# drive.net
KiCad netlist of a schematic drawn in Altium Designer
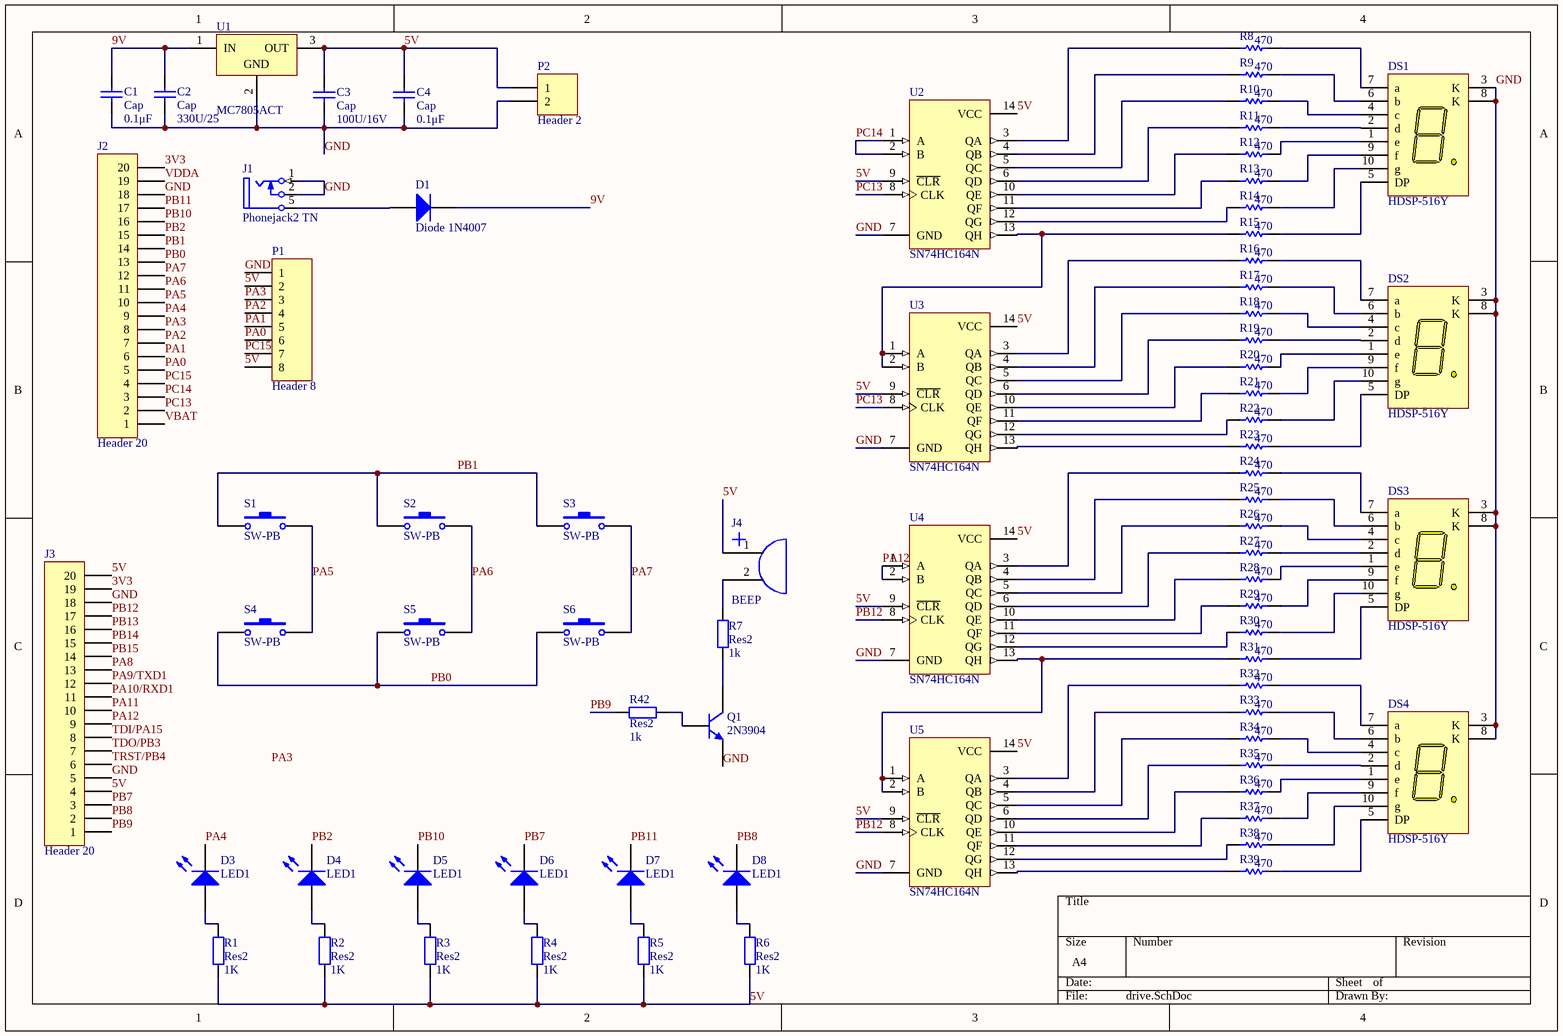
[diagram p0: drive.SchDoc]

(export (version "E")
  (design (tool "Eeschema 10.0.6"))
  (components
    (comp (ref "C1")
      (value "Cap")
      (footprint "RAD-0.3")
      (description "Capacitor")
      (fields (field (name "ALTIUM_VALUE") "0.1μF") (field (name "PUBLISHER") "Altium Limited"))
      (libsource (lib "Miscellaneous Devices") (part "Cap"))
    )
    (comp (ref "C2")
      (value "Cap")
      (footprint "RAD-0.3")
      (description "Capacitor")
      (fields (field (name "ALTIUM_VALUE") "330U/25") (field (name "PUBLISHER") "Altium Limited"))
      (libsource (lib "Miscellaneous Devices") (part "Cap"))
    )
    (comp (ref "C3")
      (value "Cap")
      (footprint "RAD-0.3")
      (description "Capacitor")
      (fields (field (name "ALTIUM_VALUE") "100U/16V") (field (name "PUBLISHER") "Altium Limited"))
      (libsource (lib "Miscellaneous Devices") (part "Cap"))
    )
    (comp (ref "C4")
      (value "Cap")
      (footprint "RAD-0.3")
      (description "Capacitor")
      (fields (field (name "ALTIUM_VALUE") "0.1μF") (field (name "PUBLISHER") "Altium Limited"))
      (libsource (lib "Miscellaneous Devices") (part "Cap"))
    )
    (comp (ref "D1")
      (value "Diode 1N4007")
      (footprint "DO-41")
      (description "1 Amp General Purpose Rectifier")
      (fields (field (name "PUBLISHER") "Altium Limited"))
      (libsource (lib "Miscellaneous Devices") (part "Diode 1N4007"))
    )
    (comp (ref "D3")
      (value "LED1")
      (footprint "LED-1")
      (description "Typical RED GaAs LED")
      (fields (field (name "PUBLISHER") "Altium Limited"))
      (libsource (lib "Miscellaneous Devices") (part "LED1"))
    )
    (comp (ref "D4")
      (value "LED1")
      (footprint "LED-1")
      (description "Typical RED GaAs LED")
      (fields (field (name "PUBLISHER") "Altium Limited"))
      (libsource (lib "Miscellaneous Devices") (part "LED1"))
    )
    (comp (ref "D5")
      (value "LED1")
      (footprint "LED-1")
      (description "Typical RED GaAs LED")
      (fields (field (name "PUBLISHER") "Altium Limited"))
      (libsource (lib "Miscellaneous Devices") (part "LED1"))
    )
    (comp (ref "D6")
      (value "LED1")
      (footprint "LED-1")
      (description "Typical RED GaAs LED")
      (fields (field (name "PUBLISHER") "Altium Limited"))
      (libsource (lib "Miscellaneous Devices") (part "LED1"))
    )
    (comp (ref "D7")
      (value "LED1")
      (footprint "LED-1")
      (description "Typical RED GaAs LED")
      (fields (field (name "PUBLISHER") "Altium Limited"))
      (libsource (lib "Miscellaneous Devices") (part "LED1"))
    )
    (comp (ref "D8")
      (value "LED1")
      (footprint "LED-1")
      (description "Typical RED GaAs LED")
      (fields (field (name "PUBLISHER") "Altium Limited"))
      (libsource (lib "Miscellaneous Devices") (part "LED1"))
    )
    (comp (ref "DS1")
      (value "HDSP-516Y")
      (footprint "Case-5")
      (description "13 mm Slim Font, Standard Current, Yellow 7-Segment Display: CC, RH DP")
      (fields (field (name "PUBLISHER") "Altium Limited"))
      (libsource (lib "Agilent LED Display 7-Segment, 1-Digit") (part "HDSP-516Y"))
    )
    (comp (ref "DS2")
      (value "HDSP-516Y")
      (footprint "Case-5")
      (description "13 mm Slim Font, Standard Current, Yellow 7-Segment Display: CC, RH DP")
      (fields (field (name "PUBLISHER") "Altium Limited"))
      (libsource (lib "Agilent LED Display 7-Segment, 1-Digit") (part "HDSP-516Y"))
    )
    (comp (ref "DS3")
      (value "HDSP-516Y")
      (footprint "Case-5")
      (description "13 mm Slim Font, Standard Current, Yellow 7-Segment Display: CC, RH DP")
      (fields (field (name "PUBLISHER") "Altium Limited"))
      (libsource (lib "Agilent LED Display 7-Segment, 1-Digit") (part "HDSP-516Y"))
    )
    (comp (ref "DS4")
      (value "HDSP-516Y")
      (footprint "Case-5")
      (description "13 mm Slim Font, Standard Current, Yellow 7-Segment Display: CC, RH DP")
      (fields (field (name "PUBLISHER") "Altium Limited"))
      (libsource (lib "Agilent LED Display 7-Segment, 1-Digit") (part "HDSP-516Y"))
    )
    (comp (ref "J1")
      (value "Phonejack2 TN")
      (footprint "DC-005")
      (description "Jack Socket, 1/4\" [6.5mm], Thru-Hole, Vertical, 2-Conductor with Tip closed")
      (fields (field (name "PUBLISHER") "Altium Limited"))
      (libsource (lib "Miscellaneous Connectors") (part "Phonejack2 TN"))
    )
    (comp (ref "J2")
      (value "Header 20")
      (footprint "HDR1X20")
      (description "Header, 20-Pin")
      (fields (field (name "PUBLISHER") "Altium Limited"))
      (libsource (lib "Miscellaneous Connectors") (part "Header 20"))
    )
    (comp (ref "J3")
      (value "Header 20")
      (footprint "HDR1X20")
      (description "Header, 20-Pin")
      (fields (field (name "PUBLISHER") "Altium Limited"))
      (libsource (lib "Miscellaneous Connectors") (part "Header 20"))
    )
    (comp (ref "J4")
      (value "BEEP")
      (footprint "Beep")
      (description "蜂鸣器")
      (libsource (lib "TSLone") (part "BEEP"))
    )
    (comp (ref "P1")
      (value "Header 8")
      (footprint "HDR1X8")
      (description "Header, 8-Pin")
      (fields (field (name "PUBLISHER") "Altium Limited"))
      (libsource (lib "Miscellaneous Connectors") (part "Header 8"))
    )
    (comp (ref "P2")
      (value "Header 2")
      (footprint "HDR1X2")
      (description "Header, 2-Pin")
      (fields (field (name "PUBLISHER") "Altium Limited"))
      (libsource (lib "Miscellaneous Connectors") (part "Header 2"))
    )
    (comp (ref "Q1")
      (value "2N3904")
      (footprint "TO-92A")
      (description "NPN General Purpose Amplifier")
      (fields (field (name "PUBLISHER") "Altium Limited"))
      (libsource (lib "Miscellaneous Devices") (part "2N3904"))
    )
    (comp (ref "R1")
      (value "Res2")
      (footprint "AXIAL-0.4")
      (description "Resistor")
      (fields (field (name "ALTIUM_VALUE") "1K") (field (name "PUBLISHER") "Altium Limited"))
      (libsource (lib "Miscellaneous Devices") (part "Res2"))
    )
    (comp (ref "R2")
      (value "Res2")
      (footprint "AXIAL-0.4")
      (description "Resistor")
      (fields (field (name "ALTIUM_VALUE") "1K") (field (name "PUBLISHER") "Altium Limited"))
      (libsource (lib "Miscellaneous Devices") (part "Res2"))
    )
    (comp (ref "R3")
      (value "Res2")
      (footprint "AXIAL-0.4")
      (description "Resistor")
      (fields (field (name "ALTIUM_VALUE") "1K") (field (name "PUBLISHER") "Altium Limited"))
      (libsource (lib "Miscellaneous Devices") (part "Res2"))
    )
    (comp (ref "R4")
      (value "Res2")
      (footprint "AXIAL-0.4")
      (description "Resistor")
      (fields (field (name "ALTIUM_VALUE") "1K") (field (name "PUBLISHER") "Altium Limited"))
      (libsource (lib "Miscellaneous Devices") (part "Res2"))
    )
    (comp (ref "R5")
      (value "Res2")
      (footprint "AXIAL-0.4")
      (description "Resistor")
      (fields (field (name "ALTIUM_VALUE") "1K") (field (name "PUBLISHER") "Altium Limited"))
      (libsource (lib "Miscellaneous Devices") (part "Res2"))
    )
    (comp (ref "R6")
      (value "Res2")
      (footprint "AXIAL-0.4")
      (description "Resistor")
      (fields (field (name "ALTIUM_VALUE") "1K") (field (name "PUBLISHER") "Altium Limited"))
      (libsource (lib "Miscellaneous Devices") (part "Res2"))
    )
    (comp (ref "R7")
      (value "Res2")
      (footprint "AXIAL-0.4")
      (description "Resistor")
      (fields (field (name "ALTIUM_VALUE") "1k") (field (name "PUBLISHER") "Altium Limited"))
      (libsource (lib "Miscellaneous Devices") (part "Res2"))
    )
    (comp (ref "R8")
      (value "470")
      (footprint "AXIAL-0.3")
      (description "Resistor")
      (fields (field (name "Comment") "Res1") (field (name "PUBLISHER") "Altium Limited"))
      (libsource (lib "Miscellaneous Devices") (part "Res1"))
    )
    (comp (ref "R9")
      (value "470")
      (footprint "AXIAL-0.3")
      (description "Resistor")
      (fields (field (name "Comment") "Res1") (field (name "PUBLISHER") "Altium Limited"))
      (libsource (lib "Miscellaneous Devices") (part "Res1"))
    )
    (comp (ref "R10")
      (value "470")
      (footprint "AXIAL-0.3")
      (description "Resistor")
      (fields (field (name "Comment") "Res1") (field (name "PUBLISHER") "Altium Limited"))
      (libsource (lib "Miscellaneous Devices") (part "Res1"))
    )
    (comp (ref "R11")
      (value "470")
      (footprint "AXIAL-0.3")
      (description "Resistor")
      (fields (field (name "Comment") "Res1") (field (name "PUBLISHER") "Altium Limited"))
      (libsource (lib "Miscellaneous Devices") (part "Res1"))
    )
    (comp (ref "R12")
      (value "470")
      (footprint "AXIAL-0.3")
      (description "Resistor")
      (fields (field (name "Comment") "Res1") (field (name "PUBLISHER") "Altium Limited"))
      (libsource (lib "Miscellaneous Devices") (part "Res1"))
    )
    (comp (ref "R13")
      (value "470")
      (footprint "AXIAL-0.3")
      (description "Resistor")
      (fields (field (name "Comment") "Res1") (field (name "PUBLISHER") "Altium Limited"))
      (libsource (lib "Miscellaneous Devices") (part "Res1"))
    )
    (comp (ref "R14")
      (value "470")
      (footprint "AXIAL-0.3")
      (description "Resistor")
      (fields (field (name "Comment") "Res1") (field (name "PUBLISHER") "Altium Limited"))
      (libsource (lib "Miscellaneous Devices") (part "Res1"))
    )
    (comp (ref "R15")
      (value "470")
      (footprint "AXIAL-0.3")
      (description "Resistor")
      (fields (field (name "Comment") "Res1") (field (name "PUBLISHER") "Altium Limited"))
      (libsource (lib "Miscellaneous Devices") (part "Res1"))
    )
    (comp (ref "R16")
      (value "470")
      (footprint "AXIAL-0.3")
      (description "Resistor")
      (fields (field (name "Comment") "Res1") (field (name "PUBLISHER") "Altium Limited"))
      (libsource (lib "Miscellaneous Devices") (part "Res1"))
    )
    (comp (ref "R17")
      (value "470")
      (footprint "AXIAL-0.3")
      (description "Resistor")
      (fields (field (name "Comment") "Res1") (field (name "PUBLISHER") "Altium Limited"))
      (libsource (lib "Miscellaneous Devices") (part "Res1"))
    )
    (comp (ref "R18")
      (value "470")
      (footprint "AXIAL-0.3")
      (description "Resistor")
      (fields (field (name "Comment") "Res1") (field (name "PUBLISHER") "Altium Limited"))
      (libsource (lib "Miscellaneous Devices") (part "Res1"))
    )
    (comp (ref "R19")
      (value "470")
      (footprint "AXIAL-0.3")
      (description "Resistor")
      (fields (field (name "Comment") "Res1") (field (name "PUBLISHER") "Altium Limited"))
      (libsource (lib "Miscellaneous Devices") (part "Res1"))
    )
    (comp (ref "R20")
      (value "470")
      (footprint "AXIAL-0.3")
      (description "Resistor")
      (fields (field (name "Comment") "Res1") (field (name "PUBLISHER") "Altium Limited"))
      (libsource (lib "Miscellaneous Devices") (part "Res1"))
    )
    (comp (ref "R21")
      (value "470")
      (footprint "AXIAL-0.3")
      (description "Resistor")
      (fields (field (name "Comment") "Res1") (field (name "PUBLISHER") "Altium Limited"))
      (libsource (lib "Miscellaneous Devices") (part "Res1"))
    )
    (comp (ref "R22")
      (value "470")
      (footprint "AXIAL-0.3")
      (description "Resistor")
      (fields (field (name "Comment") "Res1") (field (name "PUBLISHER") "Altium Limited"))
      (libsource (lib "Miscellaneous Devices") (part "Res1"))
    )
    (comp (ref "R23")
      (value "470")
      (footprint "AXIAL-0.3")
      (description "Resistor")
      (fields (field (name "Comment") "Res1") (field (name "PUBLISHER") "Altium Limited"))
      (libsource (lib "Miscellaneous Devices") (part "Res1"))
    )
    (comp (ref "R24")
      (value "470")
      (footprint "AXIAL-0.3")
      (description "Resistor")
      (fields (field (name "Comment") "Res1") (field (name "PUBLISHER") "Altium Limited"))
      (libsource (lib "Miscellaneous Devices") (part "Res1"))
    )
    (comp (ref "R25")
      (value "470")
      (footprint "AXIAL-0.3")
      (description "Resistor")
      (fields (field (name "Comment") "Res1") (field (name "PUBLISHER") "Altium Limited"))
      (libsource (lib "Miscellaneous Devices") (part "Res1"))
    )
    (comp (ref "R26")
      (value "470")
      (footprint "AXIAL-0.3")
      (description "Resistor")
      (fields (field (name "Comment") "Res1") (field (name "PUBLISHER") "Altium Limited"))
      (libsource (lib "Miscellaneous Devices") (part "Res1"))
    )
    (comp (ref "R27")
      (value "470")
      (footprint "AXIAL-0.3")
      (description "Resistor")
      (fields (field (name "Comment") "Res1") (field (name "PUBLISHER") "Altium Limited"))
      (libsource (lib "Miscellaneous Devices") (part "Res1"))
    )
    (comp (ref "R28")
      (value "470")
      (footprint "AXIAL-0.3")
      (description "Resistor")
      (fields (field (name "Comment") "Res1") (field (name "PUBLISHER") "Altium Limited"))
      (libsource (lib "Miscellaneous Devices") (part "Res1"))
    )
    (comp (ref "R29")
      (value "470")
      (footprint "AXIAL-0.3")
      (description "Resistor")
      (fields (field (name "Comment") "Res1") (field (name "PUBLISHER") "Altium Limited"))
      (libsource (lib "Miscellaneous Devices") (part "Res1"))
    )
    (comp (ref "R30")
      (value "470")
      (footprint "AXIAL-0.3")
      (description "Resistor")
      (fields (field (name "Comment") "Res1") (field (name "PUBLISHER") "Altium Limited"))
      (libsource (lib "Miscellaneous Devices") (part "Res1"))
    )
    (comp (ref "R31")
      (value "470")
      (footprint "AXIAL-0.3")
      (description "Resistor")
      (fields (field (name "Comment") "Res1") (field (name "PUBLISHER") "Altium Limited"))
      (libsource (lib "Miscellaneous Devices") (part "Res1"))
    )
    (comp (ref "R32")
      (value "470")
      (footprint "AXIAL-0.3")
      (description "Resistor")
      (fields (field (name "Comment") "Res1") (field (name "PUBLISHER") "Altium Limited"))
      (libsource (lib "Miscellaneous Devices") (part "Res1"))
    )
    (comp (ref "R33")
      (value "470")
      (footprint "AXIAL-0.3")
      (description "Resistor")
      (fields (field (name "Comment") "Res1") (field (name "PUBLISHER") "Altium Limited"))
      (libsource (lib "Miscellaneous Devices") (part "Res1"))
    )
    (comp (ref "R34")
      (value "470")
      (footprint "AXIAL-0.3")
      (description "Resistor")
      (fields (field (name "Comment") "Res1") (field (name "PUBLISHER") "Altium Limited"))
      (libsource (lib "Miscellaneous Devices") (part "Res1"))
    )
    (comp (ref "R35")
      (value "470")
      (footprint "AXIAL-0.3")
      (description "Resistor")
      (fields (field (name "Comment") "Res1") (field (name "PUBLISHER") "Altium Limited"))
      (libsource (lib "Miscellaneous Devices") (part "Res1"))
    )
    (comp (ref "R36")
      (value "470")
      (footprint "AXIAL-0.3")
      (description "Resistor")
      (fields (field (name "Comment") "Res1") (field (name "PUBLISHER") "Altium Limited"))
      (libsource (lib "Miscellaneous Devices") (part "Res1"))
    )
    (comp (ref "R37")
      (value "470")
      (footprint "AXIAL-0.3")
      (description "Resistor")
      (fields (field (name "Comment") "Res1") (field (name "PUBLISHER") "Altium Limited"))
      (libsource (lib "Miscellaneous Devices") (part "Res1"))
    )
    (comp (ref "R38")
      (value "470")
      (footprint "AXIAL-0.3")
      (description "Resistor")
      (fields (field (name "Comment") "Res1") (field (name "PUBLISHER") "Altium Limited"))
      (libsource (lib "Miscellaneous Devices") (part "Res1"))
    )
    (comp (ref "R39")
      (value "470")
      (footprint "AXIAL-0.3")
      (description "Resistor")
      (fields (field (name "Comment") "Res1") (field (name "PUBLISHER") "Altium Limited"))
      (libsource (lib "Miscellaneous Devices") (part "Res1"))
    )
    (comp (ref "R42")
      (value "Res2")
      (footprint "AXIAL-0.4")
      (description "Resistor")
      (fields (field (name "ALTIUM_VALUE") "1k") (field (name "PUBLISHER") "Altium Limited"))
      (libsource (lib "") (part "Res2_1"))
    )
    (comp (ref "S1")
      (value "SW-PB")
      (footprint "SW9")
      (description "微动开关")
      (fields (field (name "PUBLISHER") "Altium Limited"))
      (libsource (lib "TSLone") (part "SW-PB"))
    )
    (comp (ref "S2")
      (value "SW-PB")
      (footprint "SW9")
      (description "微动开关")
      (fields (field (name "PUBLISHER") "Altium Limited"))
      (libsource (lib "TSLone") (part "SW-PB"))
    )
    (comp (ref "S3")
      (value "SW-PB")
      (footprint "SW9")
      (description "微动开关")
      (fields (field (name "PUBLISHER") "Altium Limited"))
      (libsource (lib "TSLone") (part "SW-PB"))
    )
    (comp (ref "S4")
      (value "SW-PB")
      (footprint "SW9")
      (description "微动开关")
      (fields (field (name "PUBLISHER") "Altium Limited"))
      (libsource (lib "TSLone") (part "SW-PB"))
    )
    (comp (ref "S5")
      (value "SW-PB")
      (footprint "SW9")
      (description "微动开关")
      (fields (field (name "PUBLISHER") "Altium Limited"))
      (libsource (lib "TSLone") (part "SW-PB"))
    )
    (comp (ref "S6")
      (value "SW-PB")
      (footprint "SW9")
      (description "微动开关")
      (fields (field (name "PUBLISHER") "Altium Limited"))
      (libsource (lib "TSLone") (part "SW-PB"))
    )
    (comp (ref "U1")
      (value "MC7805ACT")
      (footprint "221A-06")
      (description "Three-Terminal Positive Voltage Regulator")
      (fields (field (name "PUBLISHER") "Altium Limited"))
      (libsource (lib "ON Semi Power Mgt Voltage Regulator") (part "MC7805ACT"))
    )
    (comp (ref "U2")
      (value "SN74HC164N")
      (footprint "N014")
      (description "8-Bit Parallel-Out Serial Shift Register")
      (fields (field (name "PUBLISHER") "Altium Limited"))
      (libsource (lib "TI Logic Register") (part "SN74HC164N"))
    )
    (comp (ref "U3")
      (value "SN74HC164N")
      (footprint "N014")
      (description "8-Bit Parallel-Out Serial Shift Register")
      (fields (field (name "PUBLISHER") "Altium Limited"))
      (libsource (lib "TI Logic Register") (part "SN74HC164N"))
    )
    (comp (ref "U4")
      (value "SN74HC164N")
      (footprint "N014")
      (description "8-Bit Parallel-Out Serial Shift Register")
      (fields (field (name "PUBLISHER") "Altium Limited"))
      (libsource (lib "TI Logic Register") (part "SN74HC164N"))
    )
    (comp (ref "U5")
      (value "SN74HC164N")
      (footprint "N014")
      (description "8-Bit Parallel-Out Serial Shift Register")
      (fields (field (name "PUBLISHER") "Altium Limited"))
      (libsource (lib "TI Logic Register") (part "SN74HC164N"))
    )
  )
  (nets
    (net (code "1") (name "/3V3") (class "Default")
      (node (ref "J2") (pin "20") (pinfunction "20_20") (pintype "passive"))
      (node (ref "J3") (pin "19") (pinfunction "19_19") (pintype "passive"))
    )
    (net (code "2") (name "/5V") (class "Default")
      (node (ref "C3") (pin "1") (pinfunction "1_1") (pintype "passive"))
      (node (ref "C4") (pin "1") (pinfunction "1_1") (pintype "passive"))
      (node (ref "J3") (pin "20") (pinfunction "20_20") (pintype "passive"))
      (node (ref "J3") (pin "4") (pinfunction "4_4") (pintype "passive"))
      (node (ref "J4") (pin "1") (pinfunction "0_1") (pintype "passive"))
      (node (ref "P1") (pin "2") (pinfunction "2_2") (pintype "passive"))
      (node (ref "P1") (pin "8") (pinfunction "8_8") (pintype "passive"))
      (node (ref "P2") (pin "1") (pinfunction "1_1") (pintype "passive"))
      (node (ref "R1") (pin "1") (pinfunction "1_1") (pintype "passive"))
      (node (ref "R2") (pin "1") (pinfunction "1_1") (pintype "passive"))
      (node (ref "R3") (pin "1") (pinfunction "1_1") (pintype "passive"))
      (node (ref "R4") (pin "1") (pinfunction "1_1") (pintype "passive"))
      (node (ref "R5") (pin "1") (pinfunction "1_1") (pintype "passive"))
      (node (ref "R6") (pin "1") (pinfunction "1_1") (pintype "passive"))
      (node (ref "U1") (pin "3") (pinfunction "OUT_3") (pintype "power_in"))
      (node (ref "U2") (pin "14") (pinfunction "VCC_14") (pintype "power_in"))
      (node (ref "U2") (pin "9") (pinfunction "~{CLR}_9") (pintype "input"))
      (node (ref "U3") (pin "14") (pinfunction "VCC_14") (pintype "power_in"))
      (node (ref "U3") (pin "9") (pinfunction "~{CLR}_9") (pintype "input"))
      (node (ref "U4") (pin "14") (pinfunction "VCC_14") (pintype "power_in"))
      (node (ref "U4") (pin "9") (pinfunction "~{CLR}_9") (pintype "input"))
      (node (ref "U5") (pin "14") (pinfunction "VCC_14") (pintype "power_in"))
      (node (ref "U5") (pin "9") (pinfunction "~{CLR}_9") (pintype "input"))
    )
    (net (code "3") (name "/9V") (class "Default")
      (node (ref "C1") (pin "1") (pinfunction "1_1") (pintype "passive"))
      (node (ref "C2") (pin "1") (pinfunction "1_1") (pintype "passive"))
      (node (ref "D1") (pin "2") (pinfunction "K_2") (pintype "passive"))
      (node (ref "U1") (pin "1") (pinfunction "IN_1") (pintype "power_in"))
    )
    (net (code "4") (name "/GND") (class "Default")
      (node (ref "C1") (pin "2") (pinfunction "2_2") (pintype "passive"))
      (node (ref "C2") (pin "2") (pinfunction "2_2") (pintype "passive"))
      (node (ref "C3") (pin "2") (pinfunction "2_2") (pintype "passive"))
      (node (ref "C4") (pin "2") (pinfunction "2_2") (pintype "passive"))
      (node (ref "DS1") (pin "3") (pinfunction "K_3") (pintype "passive"))
      (node (ref "DS1") (pin "8") (pinfunction "K_8") (pintype "passive"))
      (node (ref "DS2") (pin "3") (pinfunction "K_3") (pintype "passive"))
      (node (ref "DS2") (pin "8") (pinfunction "K_8") (pintype "passive"))
      (node (ref "DS3") (pin "3") (pinfunction "K_3") (pintype "passive"))
      (node (ref "DS3") (pin "8") (pinfunction "K_8") (pintype "passive"))
      (node (ref "DS4") (pin "3") (pinfunction "K_3") (pintype "passive"))
      (node (ref "DS4") (pin "8") (pinfunction "K_8") (pintype "passive"))
      (node (ref "J1") (pin "1") (pinfunction "T_1") (pintype "input"))
      (node (ref "J1") (pin "2") (pinfunction "TN_2") (pintype "passive"))
      (node (ref "J2") (pin "18") (pinfunction "18_18") (pintype "passive"))
      (node (ref "J3") (pin "18") (pinfunction "18_18") (pintype "passive"))
      (node (ref "J3") (pin "5") (pinfunction "5_5") (pintype "passive"))
      (node (ref "P1") (pin "1") (pinfunction "1_1") (pintype "passive"))
      (node (ref "P2") (pin "2") (pinfunction "2_2") (pintype "passive"))
      (node (ref "Q1") (pin "1") (pinfunction "E_1") (pintype "passive"))
      (node (ref "U1") (pin "2") (pinfunction "GND_2") (pintype "power_in"))
      (node (ref "U2") (pin "7") (pinfunction "GND_7") (pintype "power_in"))
      (node (ref "U3") (pin "7") (pinfunction "GND_7") (pintype "power_in"))
      (node (ref "U4") (pin "7") (pinfunction "GND_7") (pintype "power_in"))
      (node (ref "U5") (pin "7") (pinfunction "GND_7") (pintype "power_in"))
    )
    (net (code "5") (name "/PA0") (class "Default")
      (node (ref "J2") (pin "5") (pinfunction "5_5") (pintype "passive"))
      (node (ref "P1") (pin "6") (pinfunction "6_6") (pintype "passive"))
    )
    (net (code "6") (name "/PA1") (class "Default")
      (node (ref "J2") (pin "6") (pinfunction "6_6") (pintype "passive"))
      (node (ref "P1") (pin "5") (pinfunction "5_5") (pintype "passive"))
    )
    (net (code "7") (name "/PA2") (class "Default")
      (node (ref "J2") (pin "7") (pinfunction "7_7") (pintype "passive"))
      (node (ref "P1") (pin "4") (pinfunction "4_4") (pintype "passive"))
    )
    (net (code "8") (name "/PA3") (class "Default")
      (node (ref "J2") (pin "8") (pinfunction "8_8") (pintype "passive"))
      (node (ref "P1") (pin "3") (pinfunction "3_3") (pintype "passive"))
    )
    (net (code "9") (name "/PA4") (class "Default")
      (node (ref "D3") (pin "2") (pinfunction "K_2") (pintype "passive"))
      (node (ref "J2") (pin "9") (pinfunction "9_9") (pintype "passive"))
    )
    (net (code "10") (name "/PA5") (class "Default")
      (node (ref "J2") (pin "10") (pinfunction "10_10") (pintype "passive"))
      (node (ref "S1") (pin "2") (pinfunction "2_2") (pintype "passive"))
      (node (ref "S4") (pin "2") (pinfunction "2_2") (pintype "passive"))
    )
    (net (code "11") (name "/PA6") (class "Default")
      (node (ref "J2") (pin "11") (pinfunction "11_11") (pintype "passive"))
      (node (ref "S2") (pin "2") (pinfunction "2_2") (pintype "passive"))
      (node (ref "S5") (pin "2") (pinfunction "2_2") (pintype "passive"))
    )
    (net (code "12") (name "/PA7") (class "Default")
      (node (ref "J2") (pin "12") (pinfunction "12_12") (pintype "passive"))
      (node (ref "S3") (pin "2") (pinfunction "2_2") (pintype "passive"))
      (node (ref "S6") (pin "2") (pinfunction "2_2") (pintype "passive"))
    )
    (net (code "13") (name "/PA8") (class "Default")
      (node (ref "J3") (pin "13") (pinfunction "13_13") (pintype "passive"))
    )
    (net (code "14") (name "/PA9{slash}TXD1") (class "Default")
      (node (ref "J3") (pin "12") (pinfunction "12_12") (pintype "passive"))
    )
    (net (code "15") (name "/PA10{slash}RXD1") (class "Default")
      (node (ref "J3") (pin "11") (pinfunction "11_11") (pintype "passive"))
    )
    (net (code "16") (name "/PA11") (class "Default")
      (node (ref "J3") (pin "10") (pinfunction "10_10") (pintype "passive"))
    )
    (net (code "17") (name "/PA12") (class "Default")
      (node (ref "J3") (pin "9") (pinfunction "9_9") (pintype "passive"))
      (node (ref "U4") (pin "1") (pinfunction "A_1") (pintype "input"))
      (node (ref "U4") (pin "2") (pinfunction "B_2") (pintype "input"))
    )
    (net (code "18") (name "/PB0") (class "Default")
      (node (ref "J2") (pin "13") (pinfunction "13_13") (pintype "passive"))
      (node (ref "S4") (pin "1") (pinfunction "1_1") (pintype "passive"))
      (node (ref "S5") (pin "1") (pinfunction "1_1") (pintype "passive"))
      (node (ref "S6") (pin "1") (pinfunction "1_1") (pintype "passive"))
    )
    (net (code "19") (name "/PB1") (class "Default")
      (node (ref "J2") (pin "14") (pinfunction "14_14") (pintype "passive"))
      (node (ref "S1") (pin "1") (pinfunction "1_1") (pintype "passive"))
      (node (ref "S2") (pin "1") (pinfunction "1_1") (pintype "passive"))
      (node (ref "S3") (pin "1") (pinfunction "1_1") (pintype "passive"))
    )
    (net (code "20") (name "/PB2") (class "Default")
      (node (ref "D4") (pin "2") (pinfunction "K_2") (pintype "passive"))
      (node (ref "J2") (pin "15") (pinfunction "15_15") (pintype "passive"))
    )
    (net (code "21") (name "/PB7") (class "Default")
      (node (ref "D6") (pin "2") (pinfunction "K_2") (pintype "passive"))
      (node (ref "J3") (pin "3") (pinfunction "3_3") (pintype "passive"))
    )
    (net (code "22") (name "/PB8") (class "Default")
      (node (ref "D8") (pin "2") (pinfunction "K_2") (pintype "passive"))
      (node (ref "J3") (pin "2") (pinfunction "2_2") (pintype "passive"))
    )
    (net (code "23") (name "/PB9") (class "Default")
      (node (ref "J3") (pin "1") (pinfunction "1_1") (pintype "passive"))
      (node (ref "R42") (pin "2") (pinfunction "2_2") (pintype "passive"))
    )
    (net (code "24") (name "/PB10") (class "Default")
      (node (ref "D5") (pin "2") (pinfunction "K_2") (pintype "passive"))
      (node (ref "J2") (pin "16") (pinfunction "16_16") (pintype "passive"))
    )
    (net (code "25") (name "/PB11") (class "Default")
      (node (ref "D7") (pin "2") (pinfunction "K_2") (pintype "passive"))
      (node (ref "J2") (pin "17") (pinfunction "17_17") (pintype "passive"))
    )
    (net (code "26") (name "/PB12") (class "Default")
      (node (ref "J3") (pin "17") (pinfunction "17_17") (pintype "passive"))
      (node (ref "U4") (pin "8") (pinfunction "CLK_8") (pintype "input"))
      (node (ref "U5") (pin "8") (pinfunction "CLK_8") (pintype "input"))
    )
    (net (code "27") (name "/PB13") (class "Default")
      (node (ref "J3") (pin "16") (pinfunction "16_16") (pintype "passive"))
    )
    (net (code "28") (name "/PB14") (class "Default")
      (node (ref "J3") (pin "15") (pinfunction "15_15") (pintype "passive"))
    )
    (net (code "29") (name "/PB15") (class "Default")
      (node (ref "J3") (pin "14") (pinfunction "14_14") (pintype "passive"))
    )
    (net (code "30") (name "/PC13") (class "Default")
      (node (ref "J2") (pin "2") (pinfunction "2_2") (pintype "passive"))
      (node (ref "U2") (pin "8") (pinfunction "CLK_8") (pintype "input"))
      (node (ref "U3") (pin "8") (pinfunction "CLK_8") (pintype "input"))
    )
    (net (code "31") (name "/PC14") (class "Default")
      (node (ref "J2") (pin "3") (pinfunction "3_3") (pintype "passive"))
      (node (ref "U2") (pin "1") (pinfunction "A_1") (pintype "input"))
      (node (ref "U2") (pin "2") (pinfunction "B_2") (pintype "input"))
    )
    (net (code "32") (name "/PC15") (class "Default")
      (node (ref "J2") (pin "4") (pinfunction "4_4") (pintype "passive"))
      (node (ref "P1") (pin "7") (pinfunction "7_7") (pintype "passive"))
    )
    (net (code "33") (name "/TDI{slash}PA15") (class "Default")
      (node (ref "J3") (pin "8") (pinfunction "8_8") (pintype "passive"))
    )
    (net (code "34") (name "/TDO{slash}PB3") (class "Default")
      (node (ref "J3") (pin "7") (pinfunction "7_7") (pintype "passive"))
    )
    (net (code "35") (name "/TRST{slash}PB4") (class "Default")
      (node (ref "J3") (pin "6") (pinfunction "6_6") (pintype "passive"))
    )
    (net (code "36") (name "/VBAT") (class "Default")
      (node (ref "J2") (pin "1") (pinfunction "1_1") (pintype "passive"))
    )
    (net (code "37") (name "/VDDA") (class "Default")
      (node (ref "J2") (pin "19") (pinfunction "19_19") (pintype "passive"))
    )
    (net (code "38") (name "Net-(D1-A)") (class "Default")
      (node (ref "D1") (pin "1") (pinfunction "A_1") (pintype "passive"))
      (node (ref "J1") (pin "5") (pinfunction "S_5") (pintype "power_in"))
    )
    (net (code "39") (name "Net-(D3-A)") (class "Default")
      (node (ref "D3") (pin "1") (pinfunction "A_1") (pintype "passive"))
      (node (ref "R1") (pin "2") (pinfunction "2_2") (pintype "passive"))
    )
    (net (code "40") (name "Net-(D4-A)") (class "Default")
      (node (ref "D4") (pin "1") (pinfunction "A_1") (pintype "passive"))
      (node (ref "R2") (pin "2") (pinfunction "2_2") (pintype "passive"))
    )
    (net (code "41") (name "Net-(D5-A)") (class "Default")
      (node (ref "D5") (pin "1") (pinfunction "A_1") (pintype "passive"))
      (node (ref "R3") (pin "2") (pinfunction "2_2") (pintype "passive"))
    )
    (net (code "42") (name "Net-(D6-A)") (class "Default")
      (node (ref "D6") (pin "1") (pinfunction "A_1") (pintype "passive"))
      (node (ref "R4") (pin "2") (pinfunction "2_2") (pintype "passive"))
    )
    (net (code "43") (name "Net-(D7-A)") (class "Default")
      (node (ref "D7") (pin "1") (pinfunction "A_1") (pintype "passive"))
      (node (ref "R5") (pin "2") (pinfunction "2_2") (pintype "passive"))
    )
    (net (code "44") (name "Net-(D8-A)") (class "Default")
      (node (ref "D8") (pin "1") (pinfunction "A_1") (pintype "passive"))
      (node (ref "R6") (pin "2") (pinfunction "2_2") (pintype "passive"))
    )
    (net (code "45") (name "Net-(DS1-DP)") (class "Default")
      (node (ref "DS1") (pin "5") (pinfunction "DP_5") (pintype "passive"))
      (node (ref "R15") (pin "2") (pinfunction "2_2") (pintype "passive"))
    )
    (net (code "46") (name "Net-(DS1-a)") (class "Default")
      (node (ref "DS1") (pin "7") (pinfunction "a_7") (pintype "passive"))
      (node (ref "R8") (pin "2") (pinfunction "2_2") (pintype "passive"))
    )
    (net (code "47") (name "Net-(DS1-b)") (class "Default")
      (node (ref "DS1") (pin "6") (pinfunction "b_6") (pintype "passive"))
      (node (ref "R9") (pin "2") (pinfunction "2_2") (pintype "passive"))
    )
    (net (code "48") (name "Net-(DS1-c)") (class "Default")
      (node (ref "DS1") (pin "4") (pinfunction "c_4") (pintype "passive"))
      (node (ref "R10") (pin "2") (pinfunction "2_2") (pintype "passive"))
    )
    (net (code "49") (name "Net-(DS1-d)") (class "Default")
      (node (ref "DS1") (pin "2") (pinfunction "d_2") (pintype "passive"))
      (node (ref "R11") (pin "2") (pinfunction "2_2") (pintype "passive"))
    )
    (net (code "50") (name "Net-(DS1-e)") (class "Default")
      (node (ref "DS1") (pin "1") (pinfunction "e_1") (pintype "passive"))
      (node (ref "R12") (pin "2") (pinfunction "2_2") (pintype "passive"))
    )
    (net (code "51") (name "Net-(DS1-f)") (class "Default")
      (node (ref "DS1") (pin "9") (pinfunction "f_9") (pintype "passive"))
      (node (ref "R13") (pin "2") (pinfunction "2_2") (pintype "passive"))
    )
    (net (code "52") (name "Net-(DS1-g)") (class "Default")
      (node (ref "DS1") (pin "10") (pinfunction "g_10") (pintype "passive"))
      (node (ref "R14") (pin "2") (pinfunction "2_2") (pintype "passive"))
    )
    (net (code "53") (name "Net-(DS2-DP)") (class "Default")
      (node (ref "DS2") (pin "5") (pinfunction "DP_5") (pintype "passive"))
      (node (ref "R23") (pin "2") (pinfunction "2_2") (pintype "passive"))
    )
    (net (code "54") (name "Net-(DS2-a)") (class "Default")
      (node (ref "DS2") (pin "7") (pinfunction "a_7") (pintype "passive"))
      (node (ref "R16") (pin "2") (pinfunction "2_2") (pintype "passive"))
    )
    (net (code "55") (name "Net-(DS2-b)") (class "Default")
      (node (ref "DS2") (pin "6") (pinfunction "b_6") (pintype "passive"))
      (node (ref "R17") (pin "2") (pinfunction "2_2") (pintype "passive"))
    )
    (net (code "56") (name "Net-(DS2-c)") (class "Default")
      (node (ref "DS2") (pin "4") (pinfunction "c_4") (pintype "passive"))
      (node (ref "R18") (pin "2") (pinfunction "2_2") (pintype "passive"))
    )
    (net (code "57") (name "Net-(DS2-d)") (class "Default")
      (node (ref "DS2") (pin "2") (pinfunction "d_2") (pintype "passive"))
      (node (ref "R19") (pin "2") (pinfunction "2_2") (pintype "passive"))
    )
    (net (code "58") (name "Net-(DS2-e)") (class "Default")
      (node (ref "DS2") (pin "1") (pinfunction "e_1") (pintype "passive"))
      (node (ref "R20") (pin "2") (pinfunction "2_2") (pintype "passive"))
    )
    (net (code "59") (name "Net-(DS2-f)") (class "Default")
      (node (ref "DS2") (pin "9") (pinfunction "f_9") (pintype "passive"))
      (node (ref "R21") (pin "2") (pinfunction "2_2") (pintype "passive"))
    )
    (net (code "60") (name "Net-(DS2-g)") (class "Default")
      (node (ref "DS2") (pin "10") (pinfunction "g_10") (pintype "passive"))
      (node (ref "R22") (pin "2") (pinfunction "2_2") (pintype "passive"))
    )
    (net (code "61") (name "Net-(DS3-DP)") (class "Default")
      (node (ref "DS3") (pin "5") (pinfunction "DP_5") (pintype "passive"))
      (node (ref "R31") (pin "2") (pinfunction "2_2") (pintype "passive"))
    )
    (net (code "62") (name "Net-(DS3-a)") (class "Default")
      (node (ref "DS3") (pin "7") (pinfunction "a_7") (pintype "passive"))
      (node (ref "R24") (pin "2") (pinfunction "2_2") (pintype "passive"))
    )
    (net (code "63") (name "Net-(DS3-b)") (class "Default")
      (node (ref "DS3") (pin "6") (pinfunction "b_6") (pintype "passive"))
      (node (ref "R25") (pin "2") (pinfunction "2_2") (pintype "passive"))
    )
    (net (code "64") (name "Net-(DS3-c)") (class "Default")
      (node (ref "DS3") (pin "4") (pinfunction "c_4") (pintype "passive"))
      (node (ref "R26") (pin "2") (pinfunction "2_2") (pintype "passive"))
    )
    (net (code "65") (name "Net-(DS3-d)") (class "Default")
      (node (ref "DS3") (pin "2") (pinfunction "d_2") (pintype "passive"))
      (node (ref "R27") (pin "2") (pinfunction "2_2") (pintype "passive"))
    )
    (net (code "66") (name "Net-(DS3-e)") (class "Default")
      (node (ref "DS3") (pin "1") (pinfunction "e_1") (pintype "passive"))
      (node (ref "R28") (pin "2") (pinfunction "2_2") (pintype "passive"))
    )
    (net (code "67") (name "Net-(DS3-f)") (class "Default")
      (node (ref "DS3") (pin "9") (pinfunction "f_9") (pintype "passive"))
      (node (ref "R29") (pin "2") (pinfunction "2_2") (pintype "passive"))
    )
    (net (code "68") (name "Net-(DS3-g)") (class "Default")
      (node (ref "DS3") (pin "10") (pinfunction "g_10") (pintype "passive"))
      (node (ref "R30") (pin "2") (pinfunction "2_2") (pintype "passive"))
    )
    (net (code "69") (name "Net-(DS4-DP)") (class "Default")
      (node (ref "DS4") (pin "5") (pinfunction "DP_5") (pintype "passive"))
      (node (ref "R39") (pin "2") (pinfunction "2_2") (pintype "passive"))
    )
    (net (code "70") (name "Net-(DS4-a)") (class "Default")
      (node (ref "DS4") (pin "7") (pinfunction "a_7") (pintype "passive"))
      (node (ref "R32") (pin "2") (pinfunction "2_2") (pintype "passive"))
    )
    (net (code "71") (name "Net-(DS4-b)") (class "Default")
      (node (ref "DS4") (pin "6") (pinfunction "b_6") (pintype "passive"))
      (node (ref "R33") (pin "2") (pinfunction "2_2") (pintype "passive"))
    )
    (net (code "72") (name "Net-(DS4-c)") (class "Default")
      (node (ref "DS4") (pin "4") (pinfunction "c_4") (pintype "passive"))
      (node (ref "R34") (pin "2") (pinfunction "2_2") (pintype "passive"))
    )
    (net (code "73") (name "Net-(DS4-d)") (class "Default")
      (node (ref "DS4") (pin "2") (pinfunction "d_2") (pintype "passive"))
      (node (ref "R35") (pin "2") (pinfunction "2_2") (pintype "passive"))
    )
    (net (code "74") (name "Net-(DS4-e)") (class "Default")
      (node (ref "DS4") (pin "1") (pinfunction "e_1") (pintype "passive"))
      (node (ref "R36") (pin "2") (pinfunction "2_2") (pintype "passive"))
    )
    (net (code "75") (name "Net-(DS4-f)") (class "Default")
      (node (ref "DS4") (pin "9") (pinfunction "f_9") (pintype "passive"))
      (node (ref "R37") (pin "2") (pinfunction "2_2") (pintype "passive"))
    )
    (net (code "76") (name "Net-(DS4-g)") (class "Default")
      (node (ref "DS4") (pin "10") (pinfunction "g_10") (pintype "passive"))
      (node (ref "R38") (pin "2") (pinfunction "2_2") (pintype "passive"))
    )
    (net (code "77") (name "Net-(J4-1)") (class "Default")
      (node (ref "J4") (pin "2") (pinfunction "1_2") (pintype "passive"))
      (node (ref "R7") (pin "2") (pinfunction "2_2") (pintype "passive"))
    )
    (net (code "78") (name "Net-(Q1-B)") (class "Default")
      (node (ref "Q1") (pin "2") (pinfunction "B_2") (pintype "passive"))
      (node (ref "R42") (pin "1") (pinfunction "1_1") (pintype "passive"))
    )
    (net (code "79") (name "Net-(Q1-C)") (class "Default")
      (node (ref "Q1") (pin "3") (pinfunction "C_3") (pintype "passive"))
      (node (ref "R7") (pin "1") (pinfunction "1_1") (pintype "passive"))
    )
    (net (code "80") (name "Net-(U2-QA)") (class "Default")
      (node (ref "R8") (pin "1") (pinfunction "1_1") (pintype "passive"))
      (node (ref "U2") (pin "3") (pinfunction "QA_3") (pintype "output"))
    )
    (net (code "81") (name "Net-(U2-QB)") (class "Default")
      (node (ref "R9") (pin "1") (pinfunction "1_1") (pintype "passive"))
      (node (ref "U2") (pin "4") (pinfunction "QB_4") (pintype "output"))
    )
    (net (code "82") (name "Net-(U2-QC)") (class "Default")
      (node (ref "R10") (pin "1") (pinfunction "1_1") (pintype "passive"))
      (node (ref "U2") (pin "5") (pinfunction "QC_5") (pintype "output"))
    )
    (net (code "83") (name "Net-(U2-QD)") (class "Default")
      (node (ref "R11") (pin "1") (pinfunction "1_1") (pintype "passive"))
      (node (ref "U2") (pin "6") (pinfunction "QD_6") (pintype "output"))
    )
    (net (code "84") (name "Net-(U2-QE)") (class "Default")
      (node (ref "R12") (pin "1") (pinfunction "1_1") (pintype "passive"))
      (node (ref "U2") (pin "10") (pinfunction "QE_10") (pintype "output"))
    )
    (net (code "85") (name "Net-(U2-QF)") (class "Default")
      (node (ref "R13") (pin "1") (pinfunction "1_1") (pintype "passive"))
      (node (ref "U2") (pin "11") (pinfunction "QF_11") (pintype "output"))
    )
    (net (code "86") (name "Net-(U2-QG)") (class "Default")
      (node (ref "R14") (pin "1") (pinfunction "1_1") (pintype "passive"))
      (node (ref "U2") (pin "12") (pinfunction "QG_12") (pintype "output"))
    )
    (net (code "87") (name "Net-(U2-QH)") (class "Default")
      (node (ref "R15") (pin "1") (pinfunction "1_1") (pintype "passive"))
      (node (ref "U2") (pin "13") (pinfunction "QH_13") (pintype "output"))
      (node (ref "U3") (pin "1") (pinfunction "A_1") (pintype "input"))
      (node (ref "U3") (pin "2") (pinfunction "B_2") (pintype "input"))
    )
    (net (code "88") (name "Net-(U3-QA)") (class "Default")
      (node (ref "R16") (pin "1") (pinfunction "1_1") (pintype "passive"))
      (node (ref "U3") (pin "3") (pinfunction "QA_3") (pintype "output"))
    )
    (net (code "89") (name "Net-(U3-QB)") (class "Default")
      (node (ref "R17") (pin "1") (pinfunction "1_1") (pintype "passive"))
      (node (ref "U3") (pin "4") (pinfunction "QB_4") (pintype "output"))
    )
    (net (code "90") (name "Net-(U3-QC)") (class "Default")
      (node (ref "R18") (pin "1") (pinfunction "1_1") (pintype "passive"))
      (node (ref "U3") (pin "5") (pinfunction "QC_5") (pintype "output"))
    )
    (net (code "91") (name "Net-(U3-QD)") (class "Default")
      (node (ref "R19") (pin "1") (pinfunction "1_1") (pintype "passive"))
      (node (ref "U3") (pin "6") (pinfunction "QD_6") (pintype "output"))
    )
    (net (code "92") (name "Net-(U3-QE)") (class "Default")
      (node (ref "R20") (pin "1") (pinfunction "1_1") (pintype "passive"))
      (node (ref "U3") (pin "10") (pinfunction "QE_10") (pintype "output"))
    )
    (net (code "93") (name "Net-(U3-QF)") (class "Default")
      (node (ref "R21") (pin "1") (pinfunction "1_1") (pintype "passive"))
      (node (ref "U3") (pin "11") (pinfunction "QF_11") (pintype "output"))
    )
    (net (code "94") (name "Net-(U3-QG)") (class "Default")
      (node (ref "R22") (pin "1") (pinfunction "1_1") (pintype "passive"))
      (node (ref "U3") (pin "12") (pinfunction "QG_12") (pintype "output"))
    )
    (net (code "95") (name "Net-(U3-QH)") (class "Default")
      (node (ref "R23") (pin "1") (pinfunction "1_1") (pintype "passive"))
      (node (ref "U3") (pin "13") (pinfunction "QH_13") (pintype "output"))
    )
    (net (code "96") (name "Net-(U4-QA)") (class "Default")
      (node (ref "R24") (pin "1") (pinfunction "1_1") (pintype "passive"))
      (node (ref "U4") (pin "3") (pinfunction "QA_3") (pintype "output"))
    )
    (net (code "97") (name "Net-(U4-QB)") (class "Default")
      (node (ref "R25") (pin "1") (pinfunction "1_1") (pintype "passive"))
      (node (ref "U4") (pin "4") (pinfunction "QB_4") (pintype "output"))
    )
    (net (code "98") (name "Net-(U4-QC)") (class "Default")
      (node (ref "R26") (pin "1") (pinfunction "1_1") (pintype "passive"))
      (node (ref "U4") (pin "5") (pinfunction "QC_5") (pintype "output"))
    )
    (net (code "99") (name "Net-(U4-QD)") (class "Default")
      (node (ref "R27") (pin "1") (pinfunction "1_1") (pintype "passive"))
      (node (ref "U4") (pin "6") (pinfunction "QD_6") (pintype "output"))
    )
    (net (code "100") (name "Net-(U4-QE)") (class "Default")
      (node (ref "R28") (pin "1") (pinfunction "1_1") (pintype "passive"))
      (node (ref "U4") (pin "10") (pinfunction "QE_10") (pintype "output"))
    )
    (net (code "101") (name "Net-(U4-QF)") (class "Default")
      (node (ref "R29") (pin "1") (pinfunction "1_1") (pintype "passive"))
      (node (ref "U4") (pin "11") (pinfunction "QF_11") (pintype "output"))
    )
    (net (code "102") (name "Net-(U4-QG)") (class "Default")
      (node (ref "R30") (pin "1") (pinfunction "1_1") (pintype "passive"))
      (node (ref "U4") (pin "12") (pinfunction "QG_12") (pintype "output"))
    )
    (net (code "103") (name "Net-(U4-QH)") (class "Default")
      (node (ref "R31") (pin "1") (pinfunction "1_1") (pintype "passive"))
      (node (ref "U4") (pin "13") (pinfunction "QH_13") (pintype "output"))
      (node (ref "U5") (pin "1") (pinfunction "A_1") (pintype "input"))
      (node (ref "U5") (pin "2") (pinfunction "B_2") (pintype "input"))
    )
    (net (code "104") (name "Net-(U5-QA)") (class "Default")
      (node (ref "R32") (pin "1") (pinfunction "1_1") (pintype "passive"))
      (node (ref "U5") (pin "3") (pinfunction "QA_3") (pintype "output"))
    )
    (net (code "105") (name "Net-(U5-QB)") (class "Default")
      (node (ref "R33") (pin "1") (pinfunction "1_1") (pintype "passive"))
      (node (ref "U5") (pin "4") (pinfunction "QB_4") (pintype "output"))
    )
    (net (code "106") (name "Net-(U5-QC)") (class "Default")
      (node (ref "R34") (pin "1") (pinfunction "1_1") (pintype "passive"))
      (node (ref "U5") (pin "5") (pinfunction "QC_5") (pintype "output"))
    )
    (net (code "107") (name "Net-(U5-QD)") (class "Default")
      (node (ref "R35") (pin "1") (pinfunction "1_1") (pintype "passive"))
      (node (ref "U5") (pin "6") (pinfunction "QD_6") (pintype "output"))
    )
    (net (code "108") (name "Net-(U5-QE)") (class "Default")
      (node (ref "R36") (pin "1") (pinfunction "1_1") (pintype "passive"))
      (node (ref "U5") (pin "10") (pinfunction "QE_10") (pintype "output"))
    )
    (net (code "109") (name "Net-(U5-QF)") (class "Default")
      (node (ref "R37") (pin "1") (pinfunction "1_1") (pintype "passive"))
      (node (ref "U5") (pin "11") (pinfunction "QF_11") (pintype "output"))
    )
    (net (code "110") (name "Net-(U5-QG)") (class "Default")
      (node (ref "R38") (pin "1") (pinfunction "1_1") (pintype "passive"))
      (node (ref "U5") (pin "12") (pinfunction "QG_12") (pintype "output"))
    )
    (net (code "111") (name "Net-(U5-QH)") (class "Default")
      (node (ref "R39") (pin "1") (pinfunction "1_1") (pintype "passive"))
      (node (ref "U5") (pin "13") (pinfunction "QH_13") (pintype "output"))
    )
  )
)
